# ife19_TS_Charger.net
KiCad netlist of a schematic drawn in Altium Designer
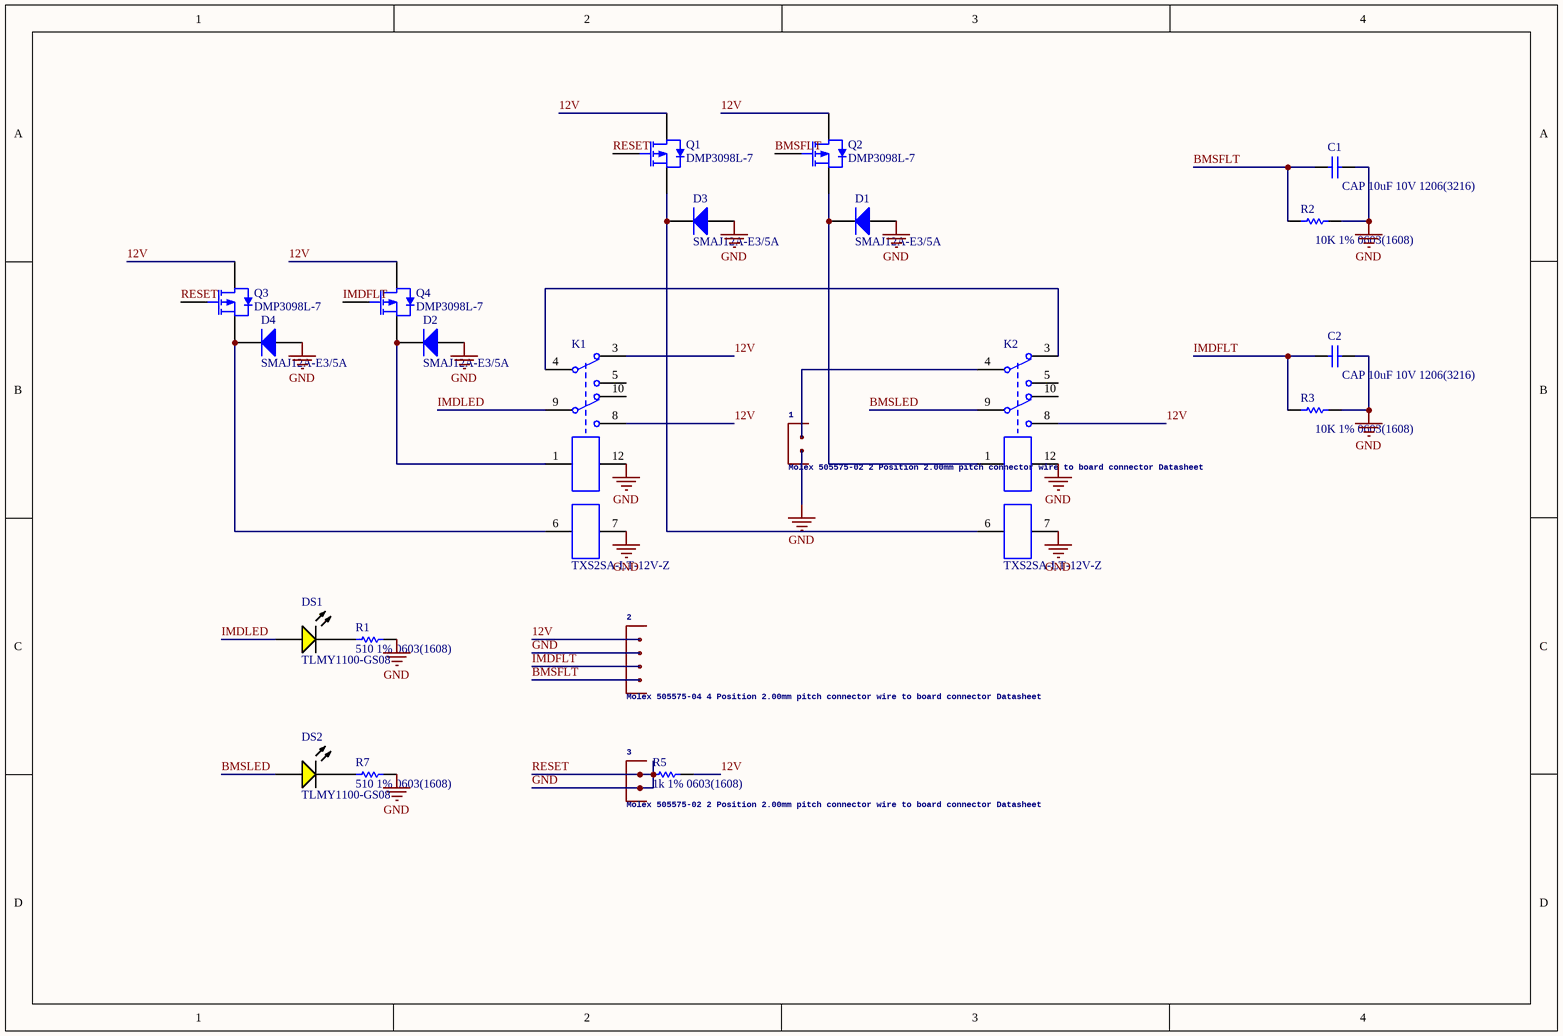
[diagram p0: ife19_TS_Charger.SchDoc]

(export (version "E")
  (design (tool "Eeschema 10.0.6"))
  (components
    (comp (ref "1")
      (value "Molex 505575-02 2 Position 2.00mm pitch connector wire to board connector Datasheet")
      (footprint "505575-02")
      (fields (field (name "LIBRARYNAME") "MOLEX Micro-Lock"))
      (libsource (lib "MOLEX Micro-Lock") (part "505575-02"))
    )
    (comp (ref "2")
      (value "Molex 505575-04 4 Position 2.00mm pitch connector wire to board connector Datasheet")
      (footprint "505575-04")
      (fields (field (name "LIBRARYNAME") "MOLEX Micro-Lock"))
      (libsource (lib "MOLEX Micro-Lock") (part "505575-04"))
    )
    (comp (ref "3")
      (value "Molex 505575-02 2 Position 2.00mm pitch connector wire to board connector Datasheet")
      (footprint "505575-02")
      (fields (field (name "LIBRARYNAME") "MOLEX Micro-Lock"))
      (libsource (lib "MOLEX Micro-Lock") (part "505575-02"))
    )
    (comp (ref "C1")
      (value "CAP 10uF 10V 1206(3216)")
      (footprint "CAPC1206(3216)130_L")
      (description "CAP 10uF 10V -20% to +80% 1206 (3216 Metric) Thickness 1.3mm SMD")
      (fields (field (name "TOLERANCE") "-20% to +80%"))
      (libsource (lib "Altium Content Vault") (part "CAP"))
    )
    (comp (ref "C2")
      (value "CAP 10uF 10V 1206(3216)")
      (footprint "CAPC1206(3216)130_L")
      (description "CAP 10uF 10V -20% to +80% 1206 (3216 Metric) Thickness 1.3mm SMD")
      (fields (field (name "TOLERANCE") "-20% to +80%"))
      (libsource (lib "Altium Content Vault") (part "CAP"))
    )
    (comp (ref "D1")
      (value "SMAJ12A-E3/5A")
      (footprint "VISH-DO-214AC-2_M")
      (fields (field (name "MANUFACTURER") "Vishay Semiconductor"))
      (libsource (lib "Altium Content Vault") (part "VISH-K1A2-2"))
    )
    (comp (ref "D2")
      (value "SMAJ12A-E3/5A")
      (footprint "VISH-DO-214AC-2_M")
      (fields (field (name "MANUFACTURER") "Vishay Semiconductor"))
      (libsource (lib "Altium Content Vault") (part "VISH-K1A2-2"))
    )
    (comp (ref "D3")
      (value "SMAJ12A-E3/5A")
      (footprint "VISH-DO-214AC-2_M")
      (fields (field (name "MANUFACTURER") "Vishay Semiconductor"))
      (libsource (lib "Altium Content Vault") (part "VISH-K1A2-2"))
    )
    (comp (ref "D4")
      (value "SMAJ12A-E3/5A")
      (footprint "VISH-DO-214AC-2_M")
      (fields (field (name "MANUFACTURER") "Vishay Semiconductor"))
      (libsource (lib "Altium Content Vault") (part "VISH-K1A2-2"))
    )
    (comp (ref "DS1")
      (value "TLMY1100-GS08")
      (footprint "VISH-TLMX1100-2_V")
      (description "Yellow LED, 20 mA, 2.1 V, -40 to 100 degC, 2-Pin SMD (0603), RoHS, Tape and Reel")
      (libsource (lib "Altium Content Vault") (part "LED-YELLOW-AK-2"))
    )
    (comp (ref "DS2")
      (value "TLMY1100-GS08")
      (footprint "VISH-TLMX1100-2_V")
      (description "Yellow LED, 20 mA, 2.1 V, -40 to 100 degC, 2-Pin SMD (0603), RoHS, Tape and Reel")
      (libsource (lib "Altium Content Vault") (part "LED-YELLOW-AK-2"))
    )
    (comp (ref "K1")
      (value "TXS2SA-LT-12V-Z")
      (footprint "PNSC-TXS2SA-L2_V")
      (description "Very High Sensitivity, Relay, 70 mW, 3 V, 10-Pin SMD, RoHS, Tape and Reel")
      (fields (field (name "MANUFACTURER") "Panasonic"))
      (libsource (lib "Altium Content Vault") (part "RELAY-DPDT-10"))
    )
    (comp (ref "K2")
      (value "TXS2SA-LT-12V-Z")
      (footprint "PNSC-TXS2SA-L2_V")
      (description "Very High Sensitivity, Relay, 70 mW, 3 V, 10-Pin SMD, RoHS, Tape and Reel")
      (fields (field (name "MANUFACTURER") "Panasonic"))
      (libsource (lib "Altium Content Vault") (part "RELAY-DPDT-10"))
    )
    (comp (ref "Q1")
      (value "DMP3098L-7")
      (footprint "DIOD-SOT23-3_V")
      (description "P-Channel Enhancement Mode MOSFET, -30 V VDS, -55 to 155 degC, 3-Pin SOT23, RoHS, Tape and Reel")
      (fields (field (name "MANUFACTURER") "Diodes Inc"))
      (libsource (lib "Altium Content Vault") (part "DIOD-PEMOS-G1S2D3-3"))
    )
    (comp (ref "Q2")
      (value "DMP3098L-7")
      (footprint "DIOD-SOT23-3_V")
      (description "P-Channel Enhancement Mode MOSFET, -30 V VDS, -55 to 155 degC, 3-Pin SOT23, RoHS, Tape and Reel")
      (fields (field (name "MANUFACTURER") "Diodes Inc"))
      (libsource (lib "Altium Content Vault") (part "DIOD-PEMOS-G1S2D3-3"))
    )
    (comp (ref "Q3")
      (value "DMP3098L-7")
      (footprint "DIOD-SOT23-3_V")
      (description "P-Channel Enhancement Mode MOSFET, -30 V VDS, -55 to 155 degC, 3-Pin SOT23, RoHS, Tape and Reel")
      (fields (field (name "MANUFACTURER") "Diodes Inc"))
      (libsource (lib "Altium Content Vault") (part "DIOD-PEMOS-G1S2D3-3"))
    )
    (comp (ref "Q4")
      (value "DMP3098L-7")
      (footprint "DIOD-SOT23-3_V")
      (description "P-Channel Enhancement Mode MOSFET, -30 V VDS, -55 to 155 degC, 3-Pin SOT23, RoHS, Tape and Reel")
      (fields (field (name "MANUFACTURER") "Diodes Inc"))
      (libsource (lib "Altium Content Vault") (part "DIOD-PEMOS-G1S2D3-3"))
    )
    (comp (ref "R1")
      (value "510 1% 0603(1608)")
      (footprint "RESC0603(1608)_L")
      (description "249K 0.1W 1% 0603 (1608 Metric)  SMD")
      (fields (field (name "POWER") "0.1 W") (field (name "TOLERANCE") "1 %"))
      (libsource (lib "Altium Content Vault") (part "RES"))
    )
    (comp (ref "R2")
      (value "10K 1% 0603(1608)")
      (footprint "RESC0603(1608)_L")
      (description "249K 0.1W 1% 0603 (1608 Metric)  SMD")
      (fields (field (name "POWER") "0.1 W") (field (name "TOLERANCE") "1 %"))
      (libsource (lib "Altium Content Vault") (part "RES"))
    )
    (comp (ref "R3")
      (value "10K 1% 0603(1608)")
      (footprint "RESC0603(1608)_L")
      (description "249K 0.1W 1% 0603 (1608 Metric)  SMD")
      (fields (field (name "POWER") "0.1 W") (field (name "TOLERANCE") "1 %"))
      (libsource (lib "Altium Content Vault") (part "RES"))
    )
    (comp (ref "R5")
      (value "1k 1% 0603(1608)")
      (footprint "RESC0603(1608)_L")
      (description "249K 0.1W 1% 0603 (1608 Metric)  SMD")
      (fields (field (name "POWER") "0.1 W") (field (name "TOLERANCE") "1 %"))
      (libsource (lib "Altium Content Vault") (part "RES"))
    )
    (comp (ref "R7")
      (value "510 1% 0603(1608)")
      (footprint "RESC0603(1608)_L")
      (description "249K 0.1W 1% 0603 (1608 Metric)  SMD")
      (fields (field (name "POWER") "0.1 W") (field (name "TOLERANCE") "1 %"))
      (libsource (lib "Altium Content Vault") (part "RES"))
    )
  )
  (nets
    (net (code "1") (name "/12V") (class "Default")
      (node (ref "2") (pin "1") (pinfunction "1_1") (pintype "passive"))
      (node (ref "K1") (pin "3") (pinfunction "3_3") (pintype "passive"))
      (node (ref "K1") (pin "8") (pinfunction "8_8") (pintype "passive"))
      (node (ref "K2") (pin "8") (pinfunction "8_8") (pintype "passive"))
      (node (ref "Q1") (pin "3") (pinfunction "D_3") (pintype "passive"))
      (node (ref "Q2") (pin "3") (pinfunction "D_3") (pintype "passive"))
      (node (ref "Q3") (pin "3") (pinfunction "D_3") (pintype "passive"))
      (node (ref "Q4") (pin "3") (pinfunction "D_3") (pintype "passive"))
      (node (ref "R5") (pin "1") (pinfunction "1_1") (pintype "passive"))
    )
    (net (code "2") (name "/BMSFLT") (class "Default")
      (node (ref "2") (pin "4") (pinfunction "4_4") (pintype "passive"))
      (node (ref "C1") (pin "1") (pinfunction "1_1") (pintype "passive"))
      (node (ref "Q2") (pin "1") (pinfunction "G_1") (pintype "passive"))
      (node (ref "R2") (pin "2") (pinfunction "2_2") (pintype "passive"))
    )
    (net (code "3") (name "/BMSLED") (class "Default")
      (node (ref "DS2") (pin "1") (pinfunction "A_1") (pintype "passive"))
      (node (ref "K2") (pin "9") (pinfunction "9_9") (pintype "passive"))
    )
    (net (code "4") (name "/IMDFLT") (class "Default")
      (node (ref "2") (pin "3") (pinfunction "3_3") (pintype "passive"))
      (node (ref "C2") (pin "1") (pinfunction "1_1") (pintype "passive"))
      (node (ref "Q4") (pin "1") (pinfunction "G_1") (pintype "passive"))
      (node (ref "R3") (pin "2") (pinfunction "2_2") (pintype "passive"))
    )
    (net (code "5") (name "/IMDLED") (class "Default")
      (node (ref "DS1") (pin "1") (pinfunction "A_1") (pintype "passive"))
      (node (ref "K1") (pin "9") (pinfunction "9_9") (pintype "passive"))
    )
    (net (code "6") (name "GND") (class "Default")
      (node (ref "1") (pin "2") (pinfunction "2_2") (pintype "passive"))
      (node (ref "2") (pin "2") (pinfunction "2_2") (pintype "passive"))
      (node (ref "3") (pin "1") (pinfunction "1_1") (pintype "passive"))
      (node (ref "3") (pin "2") (pinfunction "2_2") (pintype "passive"))
      (node (ref "C1") (pin "2") (pinfunction "2_2") (pintype "passive"))
      (node (ref "C2") (pin "2") (pinfunction "2_2") (pintype "passive"))
      (node (ref "D1") (pin "2") (pinfunction "A_2") (pintype "passive"))
      (node (ref "D2") (pin "2") (pinfunction "A_2") (pintype "passive"))
      (node (ref "D3") (pin "2") (pinfunction "A_2") (pintype "passive"))
      (node (ref "D4") (pin "2") (pinfunction "A_2") (pintype "passive"))
      (node (ref "K1") (pin "12") (pinfunction "12_12") (pintype "passive"))
      (node (ref "K1") (pin "7") (pinfunction "7_7") (pintype "passive"))
      (node (ref "K2") (pin "12") (pinfunction "12_12") (pintype "passive"))
      (node (ref "K2") (pin "7") (pinfunction "7_7") (pintype "passive"))
      (node (ref "Q1") (pin "1") (pinfunction "G_1") (pintype "passive"))
      (node (ref "Q3") (pin "1") (pinfunction "G_1") (pintype "passive"))
      (node (ref "R1") (pin "1") (pinfunction "1_1") (pintype "passive"))
      (node (ref "R2") (pin "1") (pinfunction "1_1") (pintype "passive"))
      (node (ref "R3") (pin "1") (pinfunction "1_1") (pintype "passive"))
      (node (ref "R5") (pin "2") (pinfunction "2_2") (pintype "passive"))
      (node (ref "R7") (pin "1") (pinfunction "1_1") (pintype "passive"))
    )
    (net (code "7") (name "Net-(1-Pad1)") (class "Default")
      (node (ref "1") (pin "1") (pinfunction "1_1") (pintype "passive"))
      (node (ref "K2") (pin "4") (pinfunction "4_4") (pintype "passive"))
    )
    (net (code "8") (name "Net-(D1-K)") (class "Default")
      (node (ref "D1") (pin "1") (pinfunction "K_1") (pintype "passive"))
      (node (ref "K2") (pin "1") (pinfunction "1_1") (pintype "passive"))
      (node (ref "Q2") (pin "2") (pinfunction "S_2") (pintype "passive"))
    )
    (net (code "9") (name "Net-(D2-K)") (class "Default")
      (node (ref "D2") (pin "1") (pinfunction "K_1") (pintype "passive"))
      (node (ref "K1") (pin "1") (pinfunction "1_1") (pintype "passive"))
      (node (ref "Q4") (pin "2") (pinfunction "S_2") (pintype "passive"))
    )
    (net (code "10") (name "Net-(D3-K)") (class "Default")
      (node (ref "D3") (pin "1") (pinfunction "K_1") (pintype "passive"))
      (node (ref "K2") (pin "6") (pinfunction "6_6") (pintype "passive"))
      (node (ref "Q1") (pin "2") (pinfunction "S_2") (pintype "passive"))
    )
    (net (code "11") (name "Net-(D4-K)") (class "Default")
      (node (ref "D4") (pin "1") (pinfunction "K_1") (pintype "passive"))
      (node (ref "K1") (pin "6") (pinfunction "6_6") (pintype "passive"))
      (node (ref "Q3") (pin "2") (pinfunction "S_2") (pintype "passive"))
    )
    (net (code "12") (name "Net-(DS1-K)") (class "Default")
      (node (ref "DS1") (pin "2") (pinfunction "K_2") (pintype "passive"))
      (node (ref "R1") (pin "2") (pinfunction "2_2") (pintype "passive"))
    )
    (net (code "13") (name "Net-(DS2-K)") (class "Default")
      (node (ref "DS2") (pin "2") (pinfunction "K_2") (pintype "passive"))
      (node (ref "R7") (pin "2") (pinfunction "2_2") (pintype "passive"))
    )
    (net (code "14") (name "Net-(K1-Pad4)") (class "Default")
      (node (ref "K1") (pin "4") (pinfunction "4_4") (pintype "passive"))
      (node (ref "K2") (pin "3") (pinfunction "3_3") (pintype "passive"))
    )
    (net (code "15") (name "unconnected-(K1-Pad5)") (class "Default")
      (node (ref "K1") (pin "5") (pinfunction "5_5") (pintype "passive"))
    )
    (net (code "16") (name "unconnected-(K1-Pad10)") (class "Default")
      (node (ref "K1") (pin "10") (pinfunction "10_10") (pintype "passive"))
    )
    (net (code "17") (name "unconnected-(K2-Pad5)") (class "Default")
      (node (ref "K2") (pin "5") (pinfunction "5_5") (pintype "passive"))
    )
    (net (code "18") (name "unconnected-(K2-Pad10)") (class "Default")
      (node (ref "K2") (pin "10") (pinfunction "10_10") (pintype "passive"))
    )
  )
)
